# USBDM_Kinetis.net
KiCad netlist of a schematic drawn in Altium Designer
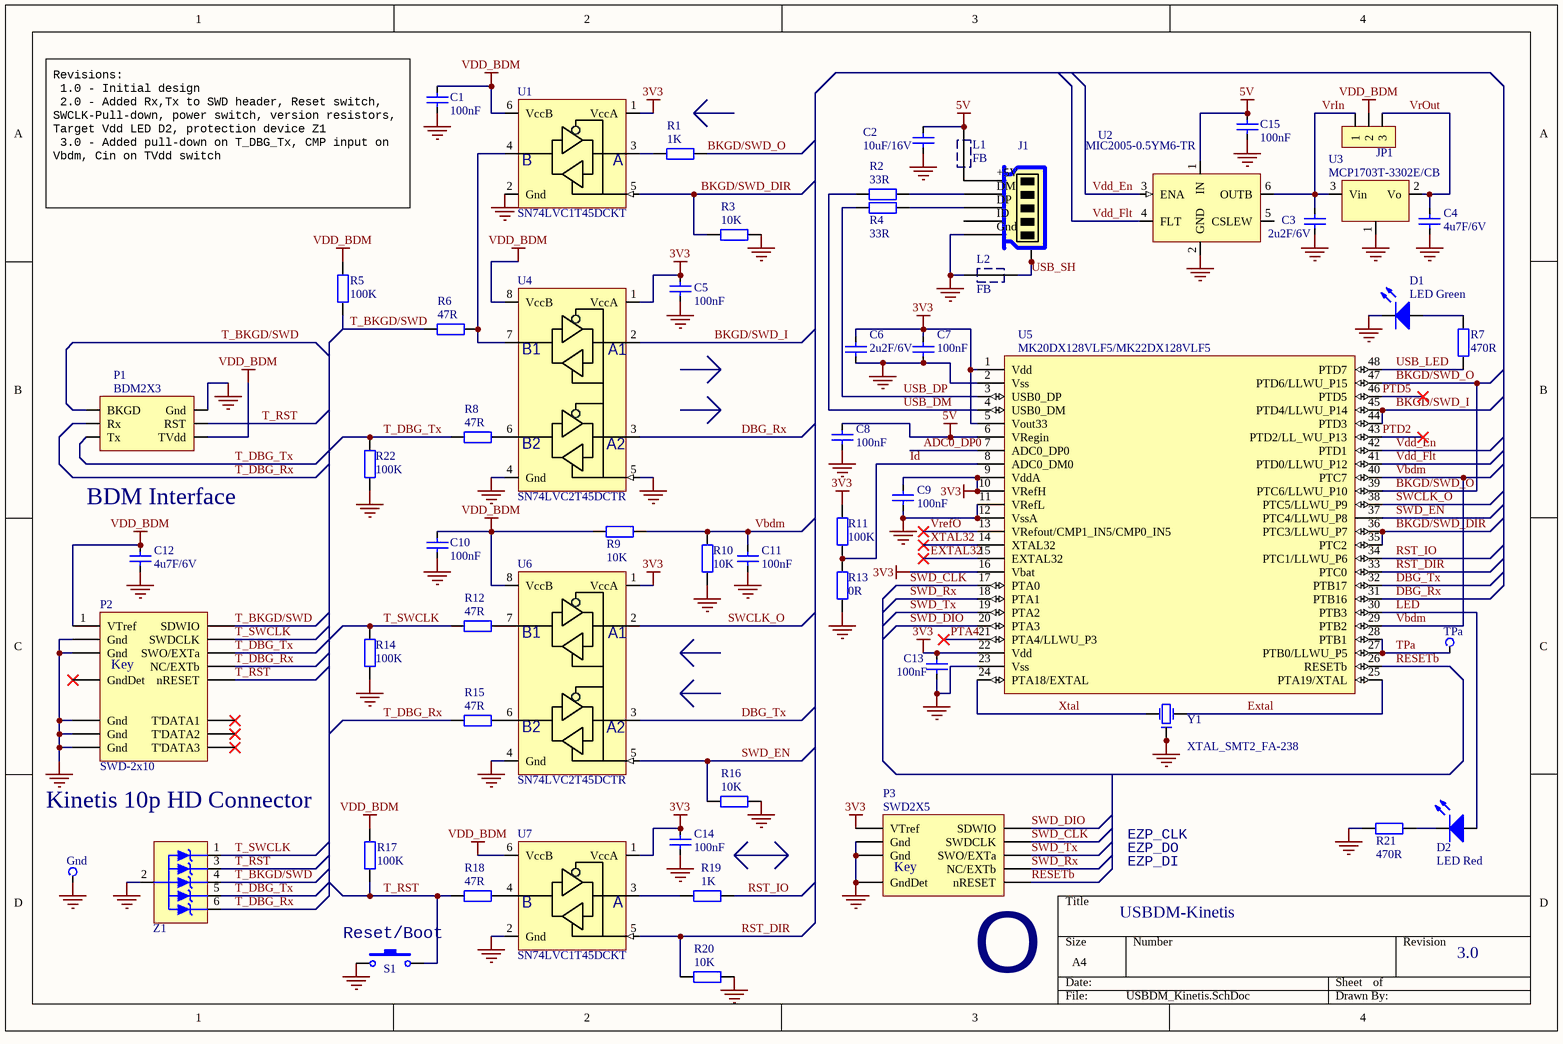
[diagram p0: USBDM_Kinetis.SchDoc]

(export (version "E")
  (design (tool "Eeschema 10.0.6"))
  (components
    (comp (ref "C1")
      (value "100nF")
      (footprint "CCNP1608-0603")
      (description "Capacitor SMT 0603")
      (fields
        (field (name "MANUFACTURER") "Generic Components")
        (field (name "PUBLISHER") "Altium Hobart Technology Centre")
      )
      (libsource (lib "MyLibrary") (part "Cap_CCNP_0603"))
    )
    (comp (ref "C2")
      (value "10uF/16V")
      (footprint "CCNP2012-0805")
      (description "Capacitor SMT 0805")
      (fields
        (field (name "MANUFACTURER") "Generic Components")
        (field (name "PUBLISHER") "Altium Hobart Technology Centre")
      )
      (libsource (lib "MyLibrary") (part "Cap_CCNP_0805"))
    )
    (comp (ref "C3")
      (value "2u2F/6V")
      (footprint "CCNP1608-0603")
      (description "Capacitor SMT 0603")
      (fields
        (field (name "MANUFACTURER") "Generic Components")
        (field (name "PUBLISHER") "Altium Hobart Technology Centre")
      )
      (libsource (lib "MyLibrary") (part "Cap_CCNP_0603"))
    )
    (comp (ref "C4")
      (value "4u7F/6V")
      (footprint "CCNP1608-0603")
      (description "Capacitor SMT 0603")
      (fields
        (field (name "MANUFACTURER") "Generic Components")
        (field (name "PUBLISHER") "Altium Hobart Technology Centre")
      )
      (libsource (lib "MyLibrary") (part "Cap_CCNP_0603"))
    )
    (comp (ref "C5")
      (value "100nF")
      (footprint "CCNP1608-0603")
      (description "Capacitor SMT 0603")
      (fields
        (field (name "MANUFACTURER") "Generic Components")
        (field (name "PUBLISHER") "Altium Hobart Technology Centre")
      )
      (libsource (lib "MyLibrary") (part "Cap_CCNP_0603"))
    )
    (comp (ref "C6")
      (value "2u2F/6V")
      (footprint "CCNP1608-0603")
      (description "Capacitor SMT 0603")
      (fields
        (field (name "MANUFACTURER") "Generic Components")
        (field (name "PUBLISHER") "Altium Hobart Technology Centre")
      )
      (libsource (lib "MyLibrary") (part "Cap_CCNP_0603"))
    )
    (comp (ref "C7")
      (value "100nF")
      (footprint "CCNP1608-0603")
      (description "Capacitor SMT 0603")
      (fields
        (field (name "MANUFACTURER") "Generic Components")
        (field (name "PUBLISHER") "Altium Hobart Technology Centre")
      )
      (libsource (lib "MyLibrary") (part "Cap_CCNP_0603"))
    )
    (comp (ref "C8")
      (value "100nF")
      (footprint "CCNP1608-0603")
      (description "Capacitor SMT 0603")
      (fields
        (field (name "MANUFACTURER") "Generic Components")
        (field (name "PUBLISHER") "Altium Hobart Technology Centre")
      )
      (libsource (lib "MyLibrary") (part "Cap_CCNP_0603"))
    )
    (comp (ref "C9")
      (value "100nF")
      (footprint "CCNP1608-0603")
      (description "Capacitor SMT 0603")
      (fields
        (field (name "MANUFACTURER") "Generic Components")
        (field (name "PUBLISHER") "Altium Hobart Technology Centre")
      )
      (libsource (lib "MyLibrary") (part "Cap_CCNP_0603"))
    )
    (comp (ref "C10")
      (value "100nF")
      (footprint "CCNP1608-0603")
      (description "Capacitor SMT 0603")
      (fields
        (field (name "MANUFACTURER") "Generic Components")
        (field (name "PUBLISHER") "Altium Hobart Technology Centre")
      )
      (libsource (lib "MyLibrary") (part "Cap_CCNP_0603"))
    )
    (comp (ref "C11")
      (value "100nF")
      (footprint "CCNP1608-0603")
      (description "Capacitor SMT 0603")
      (fields
        (field (name "MANUFACTURER") "Generic Components")
        (field (name "PUBLISHER") "Altium Hobart Technology Centre")
      )
      (libsource (lib "MyLibrary") (part "Cap_CCNP_0603"))
    )
    (comp (ref "C12")
      (value "4u7F/6V")
      (footprint "CCNP1608-0603")
      (description "Capacitor SMT 0603")
      (fields
        (field (name "MANUFACTURER") "Generic Components")
        (field (name "PUBLISHER") "Altium Hobart Technology Centre")
      )
      (libsource (lib "MyLibrary") (part "Cap_CCNP_0603"))
    )
    (comp (ref "C13")
      (value "100nF")
      (footprint "CCNP1608-0603")
      (description "Capacitor SMT 0603")
      (fields
        (field (name "MANUFACTURER") "Generic Components")
        (field (name "PUBLISHER") "Altium Hobart Technology Centre")
      )
      (libsource (lib "MyLibrary") (part "Cap_CCNP_0603"))
    )
    (comp (ref "C14")
      (value "100nF")
      (footprint "CCNP1608-0603")
      (description "Capacitor SMT 0603")
      (fields
        (field (name "MANUFACTURER") "Generic Components")
        (field (name "PUBLISHER") "Altium Hobart Technology Centre")
      )
      (libsource (lib "MyLibrary") (part "Cap_CCNP_0603"))
    )
    (comp (ref "C15")
      (value "100nF")
      (footprint "CCNP1608-0603")
      (description "Capacitor SMT 0603")
      (fields
        (field (name "MANUFACTURER") "Generic Components")
        (field (name "PUBLISHER") "Altium Hobart Technology Centre")
      )
      (libsource (lib "MyLibrary") (part "Cap"))
    )
    (comp (ref "D1")
      (value "LED Green")
      (footprint "LED1608-0603-GREEN")
      (description "LED 0603 Green")
      (fields (field (name "MANUFACTURER") "Generic Components") (field (name "PUBLISHER") "Altium Limited"))
      (libsource (lib "MyLibrary") (part "LED-0603-Green"))
    )
    (comp (ref "D2")
      (value "LED Red")
      (footprint "LED1608-0603-RED")
      (description "LED 0603 Red")
      (fields (field (name "MANUFACTURER") "Generic Components") (field (name "PUBLISHER") "Altium Limited"))
      (libsource (lib "MyLibrary") (part "LED-0603-Red"))
    )
    (comp (ref "Gnd")
      (value "TP")
      (footprint "PCBPIN - 0.9mm")
      (description "Test Point")
      (libsource (lib "MyLibrary") (part "TP"))
    )
    (comp (ref "J1")
      (value "USB_MICRO_B_CONNECTOR")
      (footprint "MOLEX - 47346-0001")
      (description "USB Micro-B Connector")
      (libsource (lib "MySchLib") (part "USB_MICRO_B_CONNECTOR"))
    )
    (comp (ref "JP1")
      (value "Header 1x3 2mm")
      (footprint "Header 1x3 (2mm)")
      (description "Header, 1x3, 2mm")
      (fields (field (name "MANUFACTURER") "Generic Components") (field (name "PUBLISHER") "Altium Limited"))
      (libsource (lib "MySchLib") (part "Header 1x3 2mm"))
    )
    (comp (ref "L1")
      (value "FB")
      (footprint "CR2012-0805")
      (description "Ferrite Bead (0805) 0.045OHM, 2A")
      (libsource (lib "MySchLib") (part "Ferrite Bead 0805"))
    )
    (comp (ref "L2")
      (value "FB")
      (footprint "CR2012-0805")
      (description "Ferrite Bead (0805) 0.045OHM, 2A")
      (libsource (lib "MySchLib") (part "Ferrite Bead 0805"))
    )
    (comp (ref "Logo1")
      (value "OSHW Logo")
      (footprint "OSHW")
      (libsource (lib "MySchLib") (part "OSHW Logo"))
    )
    (comp (ref "P1") (value "BDM2X3") (footprint "BDM") (libsource (lib "MyLibrary") (part "BDM2X3")))
    (comp (ref "P2")
      (value "SWD-2x10")
      (footprint "SWD-2x10 - reduced")
      (description "SWD Connector 2x10-Pin")
      (fields (field (name "PUBLISHER") "Altium Limited"))
      (libsource (lib "MySchLib") (part "SWD2X10-Reduced"))
    )
    (comp (ref "P3")
      (value "SWD2X5")
      (footprint "SWD-2x5")
      (description "SWD Connector 2x5-Pin")
      (fields (field (name "PUBLISHER") "Altium Limited"))
      (libsource (lib "MySchLib") (part "SWD2X5"))
    )
    (comp (ref "R1")
      (value "1K")
      (footprint "CR1608-0603")
      (description "Resistor SMT 0603")
      (fields
        (field (name "MANUFACTURER") "Generic Components")
        (field (name "PUBLISHER") "Altium Hobart Technology Centre")
      )
      (libsource (lib "") (part "Res_CR0603_5"))
    )
    (comp (ref "R2")
      (value "33R")
      (footprint "CR1608-0603")
      (description "Resistor SMT 0603")
      (fields
        (field (name "MANUFACTURER") "Generic Components")
        (field (name "PUBLISHER") "Altium Hobart Technology Centre")
      )
      (libsource (lib "") (part "Res_CR0603_2"))
    )
    (comp (ref "R3")
      (value "10K")
      (footprint "CR1608-0603")
      (description "Resistor SMT 0603")
      (fields
        (field (name "MANUFACTURER") "Generic Components")
        (field (name "PUBLISHER") "Altium Hobart Technology Centre")
      )
      (libsource (lib "") (part "Res_CR0603_4"))
    )
    (comp (ref "R4")
      (value "33R")
      (footprint "CR1608-0603")
      (description "Resistor SMT 0603")
      (fields
        (field (name "MANUFACTURER") "Generic Components")
        (field (name "PUBLISHER") "Altium Hobart Technology Centre")
      )
      (libsource (lib "") (part "Res_CR0603_2"))
    )
    (comp (ref "R5")
      (value "100K")
      (footprint "CR1608-0603")
      (description "Resistor SMT 0603")
      (fields
        (field (name "MANUFACTURER") "Generic Components")
        (field (name "PUBLISHER") "Altium Hobart Technology Centre")
      )
      (libsource (lib "") (part "Res_CR0603_6"))
    )
    (comp (ref "R6")
      (value "47R")
      (footprint "CR1608-0603")
      (description "Resistor SMT 0603")
      (fields
        (field (name "MANUFACTURER") "Generic Components")
        (field (name "PUBLISHER") "Altium Hobart Technology Centre")
      )
      (libsource (lib "") (part "Res_CR0603_3"))
    )
    (comp (ref "R7")
      (value "470R")
      (footprint "CR1608-0603")
      (description "Resistor SMT 0603")
      (fields
        (field (name "MANUFACTURER") "Generic Components")
        (field (name "PUBLISHER") "Altium Hobart Technology Centre")
      )
      (libsource (lib "") (part "Res_CR0603_5"))
    )
    (comp (ref "R8")
      (value "47R")
      (footprint "CR1608-0603")
      (description "Resistor SMT 0603")
      (fields
        (field (name "MANUFACTURER") "Generic Components")
        (field (name "PUBLISHER") "Altium Hobart Technology Centre")
      )
      (libsource (lib "") (part "Res_CR0603_3"))
    )
    (comp (ref "R9")
      (value "10K")
      (footprint "CR1608-0603")
      (description "Resistor SMT 0603")
      (fields
        (field (name "MANUFACTURER") "Generic Components")
        (field (name "PUBLISHER") "Altium Hobart Technology Centre")
      )
      (libsource (lib "") (part "Res_CR0603_3"))
    )
    (comp (ref "R10")
      (value "10K")
      (footprint "CR1608-0603")
      (description "Resistor SMT 0603")
      (fields
        (field (name "MANUFACTURER") "Generic Components")
        (field (name "PUBLISHER") "Altium Hobart Technology Centre")
      )
      (libsource (lib "") (part "Res_CR0603_5"))
    )
    (comp (ref "R11")
      (value "100K")
      (footprint "CR1608-0603")
      (description "Resistor SMT 0603")
      (fields
        (field (name "MANUFACTURER") "Generic Components")
        (field (name "PUBLISHER") "Altium Hobart Technology Centre")
      )
      (libsource (lib "MyLibrary") (part "Res_CR0603"))
    )
    (comp (ref "R12")
      (value "47R")
      (footprint "CR1608-0603")
      (description "Resistor SMT 0603")
      (fields
        (field (name "MANUFACTURER") "Generic Components")
        (field (name "PUBLISHER") "Altium Hobart Technology Centre")
      )
      (libsource (lib "") (part "Res_CR0603_3"))
    )
    (comp (ref "R13")
      (value "0R")
      (footprint "CR1608-0603")
      (description "Resistor SMT 0603")
      (fields
        (field (name "MANUFACTURER") "Generic Components")
        (field (name "PUBLISHER") "Altium Hobart Technology Centre")
      )
      (libsource (lib "MyLibrary") (part "Res_CR0603"))
    )
    (comp (ref "R14")
      (value "100K")
      (footprint "CR1608-0603")
      (description "Resistor SMT 0603")
      (fields
        (field (name "MANUFACTURER") "Generic Components")
        (field (name "PUBLISHER") "Altium Hobart Technology Centre")
      )
      (libsource (lib "") (part "Res_CR0603_1"))
    )
    (comp (ref "R15")
      (value "47R")
      (footprint "CR1608-0603")
      (description "Resistor SMT 0603")
      (fields
        (field (name "MANUFACTURER") "Generic Components")
        (field (name "PUBLISHER") "Altium Hobart Technology Centre")
      )
      (libsource (lib "") (part "Res_CR0603_3"))
    )
    (comp (ref "R16")
      (value "10K")
      (footprint "CR1608-0603")
      (description "Resistor SMT 0603")
      (fields
        (field (name "MANUFACTURER") "Generic Components")
        (field (name "PUBLISHER") "Altium Hobart Technology Centre")
      )
      (libsource (lib "") (part "Res_CR0603_4"))
    )
    (comp (ref "R17")
      (value "100K")
      (footprint "CR1608-0603")
      (description "Resistor SMT 0603")
      (fields
        (field (name "MANUFACTURER") "Generic Components")
        (field (name "PUBLISHER") "Altium Hobart Technology Centre")
      )
      (libsource (lib "") (part "Res_CR0603_6"))
    )
    (comp (ref "R18")
      (value "47R")
      (footprint "CR1608-0603")
      (description "Resistor SMT 0603")
      (fields
        (field (name "MANUFACTURER") "Generic Components")
        (field (name "PUBLISHER") "Altium Hobart Technology Centre")
      )
      (libsource (lib "") (part "Res_CR0603_3"))
    )
    (comp (ref "R19")
      (value "1K")
      (footprint "CR1608-0603")
      (description "Resistor SMT 0603")
      (fields
        (field (name "MANUFACTURER") "Generic Components")
        (field (name "PUBLISHER") "Altium Hobart Technology Centre")
      )
      (libsource (lib "") (part "Res_CR0603_3"))
    )
    (comp (ref "R20")
      (value "10K")
      (footprint "CR1608-0603")
      (description "Resistor SMT 0603")
      (fields
        (field (name "MANUFACTURER") "Generic Components")
        (field (name "PUBLISHER") "Altium Hobart Technology Centre")
      )
      (libsource (lib "") (part "Res_CR0603_4"))
    )
    (comp (ref "R21")
      (value "470R")
      (footprint "CR1608-0603")
      (description "Resistor SMT 0603")
      (fields
        (field (name "MANUFACTURER") "Generic Components")
        (field (name "PUBLISHER") "Altium Hobart Technology Centre")
      )
      (libsource (lib "") (part "Res_CR0603_4"))
    )
    (comp (ref "R22")
      (value "100K")
      (footprint "CR1608-0603")
      (description "Resistor SMT 0603")
      (fields
        (field (name "MANUFACTURER") "Generic Components")
        (field (name "PUBLISHER") "Altium Hobart Technology Centre")
      )
      (libsource (lib "") (part "Res_CR0603_1"))
    )
    (comp (ref "S1")
      (value "SW-PB-SMT-B3U-1000P-B")
      (footprint "SW_SMT_PB2-B3U-1000P-B")
      (description "Switch OMRON B3U series")
      (fields (field (name "MANUFACTURER") "Generic Components") (field (name "PUBLISHER") "Altium Limited"))
      (libsource (lib "MyLibrary") (part "SW-PB-SMT-B3U-1000P-B"))
    )
    (comp (ref "TPa")
      (value "TP")
      (footprint "PCBPIN - 0.9mm")
      (description "Test Point")
      (libsource (lib "MyLibrary") (part "TP"))
    )
    (comp (ref "U1")
      (value "SN74LVC1T45DCKT")
      (footprint "SC70_N")
      (description "Dual voltage bidirection buffer")
      (libsource (lib "MyLibrary") (part "SN74LVC1T45DCKT"))
    )
    (comp (ref "U2")
      (value "MIC2005-0.5YM6-TR")
      (footprint "SOT23-6-Power")
      (description "Power Switch")
      (libsource (lib "MySchLib") (part "MIC2005-0.5YM6-TR"))
    )
    (comp (ref "U3")
      (value "MCP1703T-3302E/CB")
      (footprint "SOT23")
      (description "3V3 LDO regulator")
      (libsource (lib "MyLibrary") (part "MCP1703T-3302E/CB"))
    )
    (comp (ref "U4")
      (value "SN74LVC2T45DCTR")
      (footprint "SSOP8_N")
      (description "Dual voltage bidirection buffer")
      (libsource (lib "MyLibrary") (part "SN74LVC2T45DCTR"))
    )
    (comp (ref "U5")
      (value "MK20DX128VLF5/MK22DX128VLF5")
      (footprint "TSQFP50P900X900-48L")
      (description "Arm Cortex M4")
      (libsource (lib "MyLibrary") (part "MK20DX128VLF5"))
    )
    (comp (ref "U6")
      (value "SN74LVC2T45DCTR")
      (footprint "SSOP8_N")
      (description "Dual voltage bidirection buffer")
      (libsource (lib "MyLibrary") (part "SN74LVC2T45DCTR"))
    )
    (comp (ref "U7")
      (value "SN74LVC1T45DCKT")
      (footprint "SC70_N")
      (description "Dual voltage bidirection buffer")
      (libsource (lib "MyLibrary") (part "SN74LVC1T45DCKT"))
    )
    (comp (ref "Y1")
      (value "XTAL_SMT2_FA-238")
      (footprint "Crystal_SMT - EPSON-FA-238")
      (description "Crystal (EPSON  Q22FA23800065 FA-238 24 MHZ 12.0PF)")
      (fields
        (field (name "MANUFACTURER") "Generic Components")
        (field (name "PUBLISHER") "Altium Hobart Technology Centre")
      )
      (libsource (lib "MyLibrary") (part "XTAL_SMT2_FA-238"))
    )
    (comp (ref "Z1")
      (value "82402305")
      (footprint "SOT23-6")
      (description "Quintuple Unipolar Protection Device (5V)")
      (libsource (lib "MySchLib") (part "82402305"))
    )
  )
  (nets
    (net (code "1") (name "/ADC0_DP0") (class "Default")
      (node (ref "U5") (pin "7") (pinfunction "ADC0_DP0_7") (pintype "passive"))
    )
    (net (code "2") (name "/BKGD{slash}SWD_DIR") (class "Default")
      (node (ref "R3") (pin "1") (pinfunction "1_1") (pintype "passive"))
      (node (ref "U1") (pin "5") (pinfunction "DIR_5") (pintype "input"))
      (node (ref "U5") (pin "35") (pinfunction "PTC2_35") (pintype "bidirectional"))
      (node (ref "U5") (pin "36") (pinfunction "PTC3/LLWU_P7_36") (pintype "bidirectional"))
    )
    (net (code "3") (name "/BKGD{slash}SWD_I") (class "Default")
      (node (ref "U4") (pin "2") (pinfunction "A1_2") (pintype "bidirectional"))
      (node (ref "U5") (pin "44") (pinfunction "PTD3_44") (pintype "bidirectional"))
      (node (ref "U5") (pin "45") (pinfunction "PTD4/LLWU_P14_45") (pintype "bidirectional"))
    )
    (net (code "4") (name "/BKGD{slash}SWD_O") (class "Default")
      (node (ref "R1") (pin "1") (pinfunction "1_1") (pintype "passive"))
      (node (ref "U5") (pin "39") (pinfunction "PTC6/LLWU_P10_39") (pintype "bidirectional"))
      (node (ref "U5") (pin "47") (pinfunction "PTD6/LLWU_P15_47") (pintype "bidirectional"))
    )
    (net (code "5") (name "/DBG_Rx") (class "Default")
      (node (ref "U4") (pin "3") (pinfunction "A2_3") (pintype "bidirectional"))
      (node (ref "U5") (pin "31") (pinfunction "PTB16_31") (pintype "bidirectional"))
    )
    (net (code "6") (name "/DBG_Tx") (class "Default")
      (node (ref "U5") (pin "32") (pinfunction "PTB17_32") (pintype "bidirectional"))
      (node (ref "U6") (pin "3") (pinfunction "A2_3") (pintype "bidirectional"))
    )
    (net (code "7") (name "/EXTAL32") (class "Default")
      (node (ref "U5") (pin "15") (pinfunction "EXTAL32_15") (pintype "passive+no_connect"))
    )
    (net (code "8") (name "/Extal") (class "Default")
      (node (ref "U5") (pin "25") (pinfunction "PTA19/XTAL_25") (pintype "bidirectional"))
      (node (ref "Y1") (pin "3") (pinfunction "OSC2_3") (pintype "passive"))
    )
    (net (code "9") (name "/Id") (class "Default")
      (node (ref "R11") (pin "1") (pinfunction "1_1") (pintype "passive"))
      (node (ref "R13") (pin "2") (pinfunction "2_2") (pintype "passive"))
      (node (ref "U5") (pin "8") (pinfunction "ADC0_DM0_8") (pintype "passive"))
    )
    (net (code "10") (name "/LED") (class "Default")
      (node (ref "D2") (pin "A") (pinfunction "A_A") (pintype "passive"))
      (node (ref "U5") (pin "30") (pinfunction "PTB3_30") (pintype "bidirectional"))
    )
    (net (code "11") (name "/PTA4") (class "Default")
      (node (ref "U5") (pin "21") (pinfunction "PTA4/LLWU_P3_21") (pintype "bidirectional+no_connect"))
    )
    (net (code "12") (name "/PTD2") (class "Default")
      (node (ref "U5") (pin "43") (pinfunction "PTD2/LL_WU_P13_43") (pintype "bidirectional+no_connect"))
    )
    (net (code "13") (name "/PTD5") (class "Default")
      (node (ref "U5") (pin "46") (pinfunction "PTD5_46") (pintype "bidirectional+no_connect"))
    )
    (net (code "14") (name "/RESETb") (class "Default")
      (node (ref "P3") (pin "10") (pinfunction "nRESET_10") (pintype "passive"))
      (node (ref "U5") (pin "26") (pinfunction "RESETb_26") (pintype "bidirectional"))
    )
    (net (code "15") (name "/RST_DIR") (class "Default")
      (node (ref "R20") (pin "1") (pinfunction "1_1") (pintype "passive"))
      (node (ref "U5") (pin "33") (pinfunction "PTC0_33") (pintype "bidirectional"))
      (node (ref "U7") (pin "5") (pinfunction "DIR_5") (pintype "input"))
    )
    (net (code "16") (name "/RST_IO") (class "Default")
      (node (ref "R19") (pin "1") (pinfunction "1_1") (pintype "passive"))
      (node (ref "U5") (pin "34") (pinfunction "PTC1/LLWU_P6_34") (pintype "bidirectional"))
    )
    (net (code "17") (name "/SWCLK_O") (class "Default")
      (node (ref "U5") (pin "38") (pinfunction "PTC5/LLWU_P9_38") (pintype "bidirectional"))
      (node (ref "U6") (pin "2") (pinfunction "A1_2") (pintype "bidirectional"))
    )
    (net (code "18") (name "/SWD_CLK") (class "Default")
      (node (ref "P3") (pin "4") (pinfunction "SWDCLK_4") (pintype "passive"))
      (node (ref "U5") (pin "17") (pinfunction "PTA0_17") (pintype "bidirectional"))
    )
    (net (code "19") (name "/SWD_DIO") (class "Default")
      (node (ref "P3") (pin "2") (pinfunction "SDWIO_2") (pintype "passive"))
      (node (ref "U5") (pin "20") (pinfunction "PTA3_20") (pintype "bidirectional"))
    )
    (net (code "20") (name "/SWD_EN") (class "Default")
      (node (ref "R16") (pin "1") (pinfunction "1_1") (pintype "passive"))
      (node (ref "U5") (pin "37") (pinfunction "PTC4/LLWU_P8_37") (pintype "power_in"))
      (node (ref "U6") (pin "5") (pinfunction "DIR_5") (pintype "input"))
    )
    (net (code "21") (name "/SWD_Rx") (class "Default")
      (node (ref "P3") (pin "8") (pinfunction "NC/EXTb_8") (pintype "passive"))
      (node (ref "U5") (pin "18") (pinfunction "PTA1_18") (pintype "bidirectional"))
    )
    (net (code "22") (name "/SWD_Tx") (class "Default")
      (node (ref "P3") (pin "6") (pinfunction "SWO/EXTa_6") (pintype "passive"))
      (node (ref "U5") (pin "19") (pinfunction "PTA2_19") (pintype "bidirectional"))
    )
    (net (code "23") (name "/TPa") (class "Default")
      (node (ref "TPa") (pin "1") (pinfunction "TP_1") (pintype "passive"))
      (node (ref "U5") (pin "27") (pinfunction "PTB0/LLWU_P5_27") (pintype "bidirectional"))
      (node (ref "U5") (pin "28") (pinfunction "PTB1_28") (pintype "bidirectional"))
    )
    (net (code "24") (name "/T_BKGD{slash}SWD") (class "Default")
      (node (ref "P1") (pin "1") (pinfunction "BKGD_1") (pintype "passive"))
      (node (ref "P2") (pin "2") (pinfunction "SDWIO_2") (pintype "passive"))
      (node (ref "R5") (pin "2") (pinfunction "2_2") (pintype "passive"))
      (node (ref "R6") (pin "2") (pinfunction "2_2") (pintype "passive"))
      (node (ref "Z1") (pin "4") (pintype "passive"))
    )
    (net (code "25") (name "/T_DBG_Rx") (class "Default")
      (node (ref "P1") (pin "3") (pinfunction "Rx_3") (pintype "passive"))
      (node (ref "P2") (pin "8") (pinfunction "NC/EXTb_8") (pintype "passive"))
      (node (ref "R15") (pin "2") (pinfunction "2_2") (pintype "passive"))
      (node (ref "Z1") (pin "6") (pintype "passive"))
    )
    (net (code "26") (name "/T_DBG_Tx") (class "Default")
      (node (ref "P1") (pin "5") (pinfunction "Tx_5") (pintype "passive"))
      (node (ref "P2") (pin "6") (pinfunction "SWO/EXTa_6") (pintype "passive"))
      (node (ref "R22") (pin "2") (pinfunction "2_2") (pintype "passive"))
      (node (ref "R8") (pin "2") (pinfunction "2_2") (pintype "passive"))
      (node (ref "Z1") (pin "5") (pintype "passive"))
    )
    (net (code "27") (name "/T_RST") (class "Default")
      (node (ref "P1") (pin "4") (pinfunction "RST_4") (pintype "passive"))
      (node (ref "P2") (pin "10") (pinfunction "nRESET_10") (pintype "passive"))
      (node (ref "R17") (pin "2") (pinfunction "2_2") (pintype "passive"))
      (node (ref "R18") (pin "2") (pinfunction "2_2") (pintype "passive"))
      (node (ref "S1") (pin "2") (pinfunction "2_2") (pintype "passive"))
      (node (ref "Z1") (pin "3") (pintype "passive"))
    )
    (net (code "28") (name "/T_SWCLK") (class "Default")
      (node (ref "P2") (pin "4") (pinfunction "SWDCLK_4") (pintype "passive"))
      (node (ref "R12") (pin "2") (pinfunction "2_2") (pintype "passive"))
      (node (ref "R14") (pin "2") (pinfunction "2_2") (pintype "passive"))
      (node (ref "Z1") (pin "1") (pintype "passive"))
    )
    (net (code "29") (name "/USB_DM") (class "Default")
      (node (ref "R2") (pin "2") (pinfunction "2_2") (pintype "passive"))
      (node (ref "U5") (pin "4") (pinfunction "USB0_DM_4") (pintype "bidirectional"))
    )
    (net (code "30") (name "/USB_DP") (class "Default")
      (node (ref "R4") (pin "2") (pinfunction "2_2") (pintype "passive"))
      (node (ref "U5") (pin "3") (pinfunction "USB0_DP_3") (pintype "bidirectional"))
    )
    (net (code "31") (name "/USB_LED") (class "Default")
      (node (ref "R7") (pin "2") (pinfunction "2_2") (pintype "passive"))
      (node (ref "U5") (pin "48") (pinfunction "PTD7_48") (pintype "bidirectional"))
    )
    (net (code "32") (name "/USB_SH") (class "Default")
      (node (ref "J1") (pin "S1") (pinfunction "USBShd_S1") (pintype "passive"))
      (node (ref "J1") (pin "S2") (pinfunction "USBShd_S2") (pintype "passive"))
      (node (ref "J1") (pin "S3") (pinfunction "USBShd_S3") (pintype "passive"))
      (node (ref "J1") (pin "S4") (pinfunction "USBShd_S4") (pintype "passive"))
      (node (ref "J1") (pin "S5") (pinfunction "USBShd_S5") (pintype "passive"))
      (node (ref "J1") (pin "S6") (pinfunction "USBShd_S6") (pintype "passive"))
      (node (ref "L2") (pin "1") (pinfunction "1_1") (pintype "passive"))
    )
    (net (code "33") (name "/Vbdm") (class "Default")
      (node (ref "C11") (pin "2") (pinfunction "2_2") (pintype "passive"))
      (node (ref "R10") (pin "1") (pinfunction "1_1") (pintype "passive"))
      (node (ref "R9") (pin "1") (pinfunction "1_1") (pintype "passive"))
      (node (ref "U5") (pin "29") (pinfunction "PTB2_29") (pintype "bidirectional"))
      (node (ref "U5") (pin "40") (pinfunction "PTC7_40") (pintype "bidirectional"))
    )
    (net (code "34") (name "/Vdd_En") (class "Default")
      (node (ref "U2") (pin "3") (pinfunction "ENA_3") (pintype "input"))
      (node (ref "U5") (pin "42") (pinfunction "PTD1_42") (pintype "bidirectional"))
    )
    (net (code "35") (name "/Vdd_Flt") (class "Default")
      (node (ref "U2") (pin "4") (pinfunction "FLT_4") (pintype "open_collector"))
      (node (ref "U5") (pin "41") (pinfunction "PTD0/LLWU_P12_41") (pintype "bidirectional"))
    )
    (net (code "36") (name "/VrIn") (class "Default")
      (node (ref "C3") (pin "2") (pinfunction "2_2") (pintype "passive"))
      (node (ref "JP1") (pin "1") (pinfunction "1_1") (pintype "passive"))
      (node (ref "U2") (pin "6") (pinfunction "OUTB_6") (pintype "passive"))
      (node (ref "U3") (pin "3") (pinfunction "Vin_3") (pintype "passive"))
    )
    (net (code "37") (name "/VrOut") (class "Default")
      (node (ref "C4") (pin "2") (pinfunction "2_2") (pintype "passive"))
      (node (ref "JP1") (pin "3") (pinfunction "3_3") (pintype "passive"))
      (node (ref "U3") (pin "2") (pinfunction "Vo_2") (pintype "passive"))
    )
    (net (code "38") (name "/VrefO") (class "Default")
      (node (ref "U5") (pin "13") (pinfunction "VRefout/CMP1_IN5/CMP0_IN5_13") (pintype "passive+no_connect"))
    )
    (net (code "39") (name "/XTAL32") (class "Default")
      (node (ref "U5") (pin "14") (pinfunction "XTAL32_14") (pintype "passive+no_connect"))
    )
    (net (code "40") (name "/Xtal") (class "Default")
      (node (ref "U5") (pin "24") (pinfunction "PTA18/EXTAL_24") (pintype "bidirectional"))
      (node (ref "Y1") (pin "1") (pinfunction "OSC1_1") (pintype "passive"))
    )
    (net (code "41") (name "3V3") (class "Default")
      (node (ref "C13") (pin "2") (pinfunction "2_2") (pintype "passive"))
      (node (ref "C14") (pin "2") (pinfunction "2_2") (pintype "passive"))
      (node (ref "C5") (pin "2") (pinfunction "2_2") (pintype "passive"))
      (node (ref "C6") (pin "2") (pinfunction "2_2") (pintype "passive"))
      (node (ref "C7") (pin "2") (pinfunction "2_2") (pintype "passive"))
      (node (ref "C9") (pin "2") (pinfunction "2_2") (pintype "passive"))
      (node (ref "P3") (pin "1") (pinfunction "VTref_1") (pintype "passive"))
      (node (ref "R11") (pin "2") (pinfunction "2_2") (pintype "passive"))
      (node (ref "U1") (pin "1") (pinfunction "VccA_1") (pintype "power_in"))
      (node (ref "U4") (pin "1") (pinfunction "VccA_1") (pintype "power_in"))
      (node (ref "U5") (pin "1") (pinfunction "Vdd_1") (pintype "power_in"))
      (node (ref "U5") (pin "10") (pinfunction "VRefH_10") (pintype "passive"))
      (node (ref "U5") (pin "16") (pinfunction "Vbat_16") (pintype "passive"))
      (node (ref "U5") (pin "22") (pinfunction "Vdd_22") (pintype "power_in"))
      (node (ref "U5") (pin "5") (pinfunction "Vout33_5") (pintype "power_in"))
      (node (ref "U5") (pin "9") (pinfunction "VddA_9") (pintype "power_in"))
      (node (ref "U6") (pin "1") (pinfunction "VccA_1") (pintype "power_in"))
      (node (ref "U7") (pin "1") (pinfunction "VccA_1") (pintype "power_in"))
    )
    (net (code "42") (name "5V") (class "Default")
      (node (ref "C15") (pin "1") (pinfunction "1_1") (pintype "passive"))
      (node (ref "C2") (pin "2") (pinfunction "2_2") (pintype "passive"))
      (node (ref "C8") (pin "2") (pinfunction "2_2") (pintype "passive"))
      (node (ref "L1") (pin "2") (pinfunction "2_2") (pintype "passive"))
      (node (ref "U2") (pin "1") (pinfunction "IN_1") (pintype "passive"))
      (node (ref "U5") (pin "6") (pinfunction "VRegin_6") (pintype "passive"))
    )
    (net (code "43") (name "GND") (class "Default")
      (node (ref "C1") (pin "1") (pinfunction "1_1") (pintype "passive"))
      (node (ref "C10") (pin "1") (pinfunction "1_1") (pintype "passive"))
      (node (ref "C11") (pin "1") (pinfunction "1_1") (pintype "passive"))
      (node (ref "C12") (pin "1") (pinfunction "1_1") (pintype "passive"))
      (node (ref "C13") (pin "1") (pinfunction "1_1") (pintype "passive"))
      (node (ref "C14") (pin "1") (pinfunction "1_1") (pintype "passive"))
      (node (ref "C15") (pin "2") (pinfunction "2_2") (pintype "passive"))
      (node (ref "C2") (pin "1") (pinfunction "1_1") (pintype "passive"))
      (node (ref "C3") (pin "1") (pinfunction "1_1") (pintype "passive"))
      (node (ref "C4") (pin "1") (pinfunction "1_1") (pintype "passive"))
      (node (ref "C5") (pin "1") (pinfunction "1_1") (pintype "passive"))
      (node (ref "C6") (pin "1") (pinfunction "1_1") (pintype "passive"))
      (node (ref "C7") (pin "1") (pinfunction "1_1") (pintype "passive"))
      (node (ref "C8") (pin "1") (pinfunction "1_1") (pintype "passive"))
      (node (ref "C9") (pin "1") (pinfunction "1_1") (pintype "passive"))
      (node (ref "D1") (pin "K") (pinfunction "K_K") (pintype "passive"))
      (node (ref "Gnd") (pin "1") (pinfunction "TP_1") (pintype "passive"))
      (node (ref "J1") (pin "G") (pinfunction "USBGnd_G") (pintype "passive"))
      (node (ref "L2") (pin "2") (pinfunction "2_2") (pintype "passive"))
      (node (ref "P1") (pin "2") (pinfunction "Gnd_2") (pintype "passive"))
      (node (ref "P2") (pin "15") (pinfunction "Gnd_15") (pintype "passive"))
      (node (ref "P2") (pin "17") (pinfunction "Gnd_17") (pintype "passive"))
      (node (ref "P2") (pin "19") (pinfunction "Gnd_19") (pintype "passive"))
      (node (ref "P2") (pin "3") (pinfunction "Gnd_3") (pintype "passive"))
      (node (ref "P2") (pin "5") (pinfunction "Gnd_5") (pintype "passive"))
      (node (ref "P3") (pin "3") (pinfunction "Gnd_3") (pintype "passive"))
      (node (ref "P3") (pin "5") (pinfunction "Gnd_5") (pintype "passive"))
      (node (ref "P3") (pin "9") (pinfunction "GndDet_9") (pintype "passive"))
      (node (ref "R10") (pin "2") (pinfunction "2_2") (pintype "passive"))
      (node (ref "R13") (pin "1") (pinfunction "1_1") (pintype "passive"))
      (node (ref "R14") (pin "1") (pinfunction "1_1") (pintype "passive"))
      (node (ref "R16") (pin "2") (pinfunction "2_2") (pintype "passive"))
      (node (ref "R20") (pin "2") (pinfunction "2_2") (pintype "passive"))
      (node (ref "R21") (pin "1") (pinfunction "1_1") (pintype "passive"))
      (node (ref "R22") (pin "1") (pinfunction "1_1") (pintype "passive"))
      (node (ref "R3") (pin "2") (pinfunction "2_2") (pintype "passive"))
      (node (ref "S1") (pin "1") (pinfunction "1_1") (pintype "passive"))
      (node (ref "U1") (pin "2") (pinfunction "Gnd_2") (pintype "power_in"))
      (node (ref "U2") (pin "2") (pinfunction "GND_2") (pintype "power_in"))
      (node (ref "U3") (pin "1") (pinfunction "Gnd_1") (pintype "passive"))
      (node (ref "U4") (pin "4") (pinfunction "Gnd_4") (pintype "power_in"))
      (node (ref "U4") (pin "5") (pinfunction "DIR_5") (pintype "input"))
      (node (ref "U5") (pin "11") (pinfunction "VRefL_11") (pintype "passive"))
      (node (ref "U5") (pin "12") (pinfunction "VssA_12") (pintype "power_in"))
      (node (ref "U5") (pin "2") (pinfunction "Vss_2") (pintype "power_in"))
      (node (ref "U5") (pin "23") (pinfunction "Vss_23") (pintype "power_in"))
      (node (ref "U6") (pin "4") (pinfunction "Gnd_4") (pintype "power_in"))
      (node (ref "U7") (pin "2") (pinfunction "Gnd_2") (pintype "power_in"))
      (node (ref "Y1") (pin "2") (pinfunction "Gnd_2") (pintype "passive"))
      (node (ref "Y1") (pin "4") (pinfunction "Gnd_4") (pintype "passive"))
      (node (ref "Z1") (pin "2") (pintype "passive"))
    )
    (net (code "44") (name "Net-(D1-PadA)") (class "Default")
      (node (ref "D1") (pin "A") (pinfunction "A_A") (pintype "passive"))
      (node (ref "R7") (pin "1") (pinfunction "1_1") (pintype "passive"))
    )
    (net (code "45") (name "Net-(D2-PadK)") (class "Default")
      (node (ref "D2") (pin "K") (pinfunction "K_K") (pintype "passive"))
      (node (ref "R21") (pin "2") (pinfunction "2_2") (pintype "passive"))
    )
    (net (code "46") (name "Net-(J1-USB+5v)") (class "Default")
      (node (ref "J1") (pin "VBUS") (pinfunction "USB+5v_VBUS") (pintype "power_in"))
      (node (ref "L1") (pin "1") (pinfunction "1_1") (pintype "passive"))
    )
    (net (code "47") (name "Net-(J1-USBDM)") (class "Default")
      (node (ref "J1") (pin "D-") (pinfunction "USBDM_D-") (pintype "passive"))
      (node (ref "R2") (pin "1") (pinfunction "1_1") (pintype "passive"))
    )
    (net (code "48") (name "Net-(J1-USBDP)") (class "Default")
      (node (ref "J1") (pin "D+") (pinfunction "USBDP_D+") (pintype "passive"))
      (node (ref "R4") (pin "1") (pinfunction "1_1") (pintype "passive"))
    )
    (net (code "49") (name "Net-(U1-A)") (class "Default")
      (node (ref "R1") (pin "2") (pinfunction "2_2") (pintype "passive"))
      (node (ref "U1") (pin "3") (pinfunction "A_3") (pintype "bidirectional"))
    )
    (net (code "50") (name "Net-(U1-B)") (class "Default")
      (node (ref "R6") (pin "1") (pinfunction "1_1") (pintype "passive"))
      (node (ref "U1") (pin "4") (pinfunction "B_4") (pintype "bidirectional"))
      (node (ref "U4") (pin "7") (pinfunction "B1_7") (pintype "bidirectional"))
    )
    (net (code "51") (name "Net-(U4-B2)") (class "Default")
      (node (ref "R8") (pin "1") (pinfunction "1_1") (pintype "passive"))
      (node (ref "U4") (pin "6") (pinfunction "B2_6") (pintype "bidirectional"))
    )
    (net (code "52") (name "Net-(U6-B1)") (class "Default")
      (node (ref "R12") (pin "1") (pinfunction "1_1") (pintype "passive"))
      (node (ref "U6") (pin "7") (pinfunction "B1_7") (pintype "bidirectional"))
    )
    (net (code "53") (name "Net-(U6-B2)") (class "Default")
      (node (ref "R15") (pin "1") (pinfunction "1_1") (pintype "passive"))
      (node (ref "U6") (pin "6") (pinfunction "B2_6") (pintype "bidirectional"))
    )
    (net (code "54") (name "Net-(U7-A)") (class "Default")
      (node (ref "R19") (pin "2") (pinfunction "2_2") (pintype "passive"))
      (node (ref "U7") (pin "3") (pinfunction "A_3") (pintype "bidirectional"))
    )
    (net (code "55") (name "Net-(U7-B)") (class "Default")
      (node (ref "R18") (pin "1") (pinfunction "1_1") (pintype "passive"))
      (node (ref "U7") (pin "4") (pinfunction "B_4") (pintype "bidirectional"))
    )
    (net (code "56") (name "VDD_BDM") (class "Default")
      (node (ref "C1") (pin "2") (pinfunction "2_2") (pintype "passive"))
      (node (ref "C10") (pin "2") (pinfunction "2_2") (pintype "passive"))
      (node (ref "C12") (pin "2") (pinfunction "2_2") (pintype "passive"))
      (node (ref "JP1") (pin "2") (pinfunction "2_2") (pintype "passive"))
      (node (ref "P1") (pin "6") (pinfunction "TVdd_6") (pintype "passive"))
      (node (ref "P2") (pin "1") (pinfunction "VTref_1") (pintype "passive"))
      (node (ref "R17") (pin "1") (pinfunction "1_1") (pintype "passive"))
      (node (ref "R5") (pin "1") (pinfunction "1_1") (pintype "passive"))
      (node (ref "R9") (pin "2") (pinfunction "2_2") (pintype "passive"))
      (node (ref "U1") (pin "6") (pinfunction "VccB_6") (pintype "power_in"))
      (node (ref "U4") (pin "8") (pinfunction "VccB_8") (pintype "power_in"))
      (node (ref "U6") (pin "8") (pinfunction "VccB_8") (pintype "power_in"))
      (node (ref "U7") (pin "6") (pinfunction "VccB_6") (pintype "power_in"))
    )
    (net (code "57") (name "unconnected-(J1-USB_ID-PadID)") (class "Default")
      (node (ref "J1") (pin "ID") (pinfunction "USB_ID_ID") (pintype "passive"))
    )
    (net (code "58") (name "unconnected-(P2-GndDet-Pad9)") (class "Default")
      (node (ref "P2") (pin "9") (pinfunction "GndDet_9") (pintype "passive+no_connect"))
    )
    (net (code "59") (name "unconnected-(P2-T'DATA1-Pad16)") (class "Default")
      (node (ref "P2") (pin "16") (pinfunction "T'DATA1_16") (pintype "passive+no_connect"))
    )
    (net (code "60") (name "unconnected-(P2-T'DATA2-Pad18)") (class "Default")
      (node (ref "P2") (pin "18") (pinfunction "T'DATA2_18") (pintype "passive+no_connect"))
    )
    (net (code "61") (name "unconnected-(P2-T'DATA3-Pad20)") (class "Default")
      (node (ref "P2") (pin "20") (pinfunction "T'DATA3_20") (pintype "passive+no_connect"))
    )
    (net (code "62") (name "unconnected-(U2-CSLEW-Pad5)") (class "Default")
      (node (ref "U2") (pin "5") (pinfunction "CSLEW_5") (pintype "passive"))
    )
  )
)
